# TinyArduino.net
KiCad netlist of a schematic drawn in Altium Designer
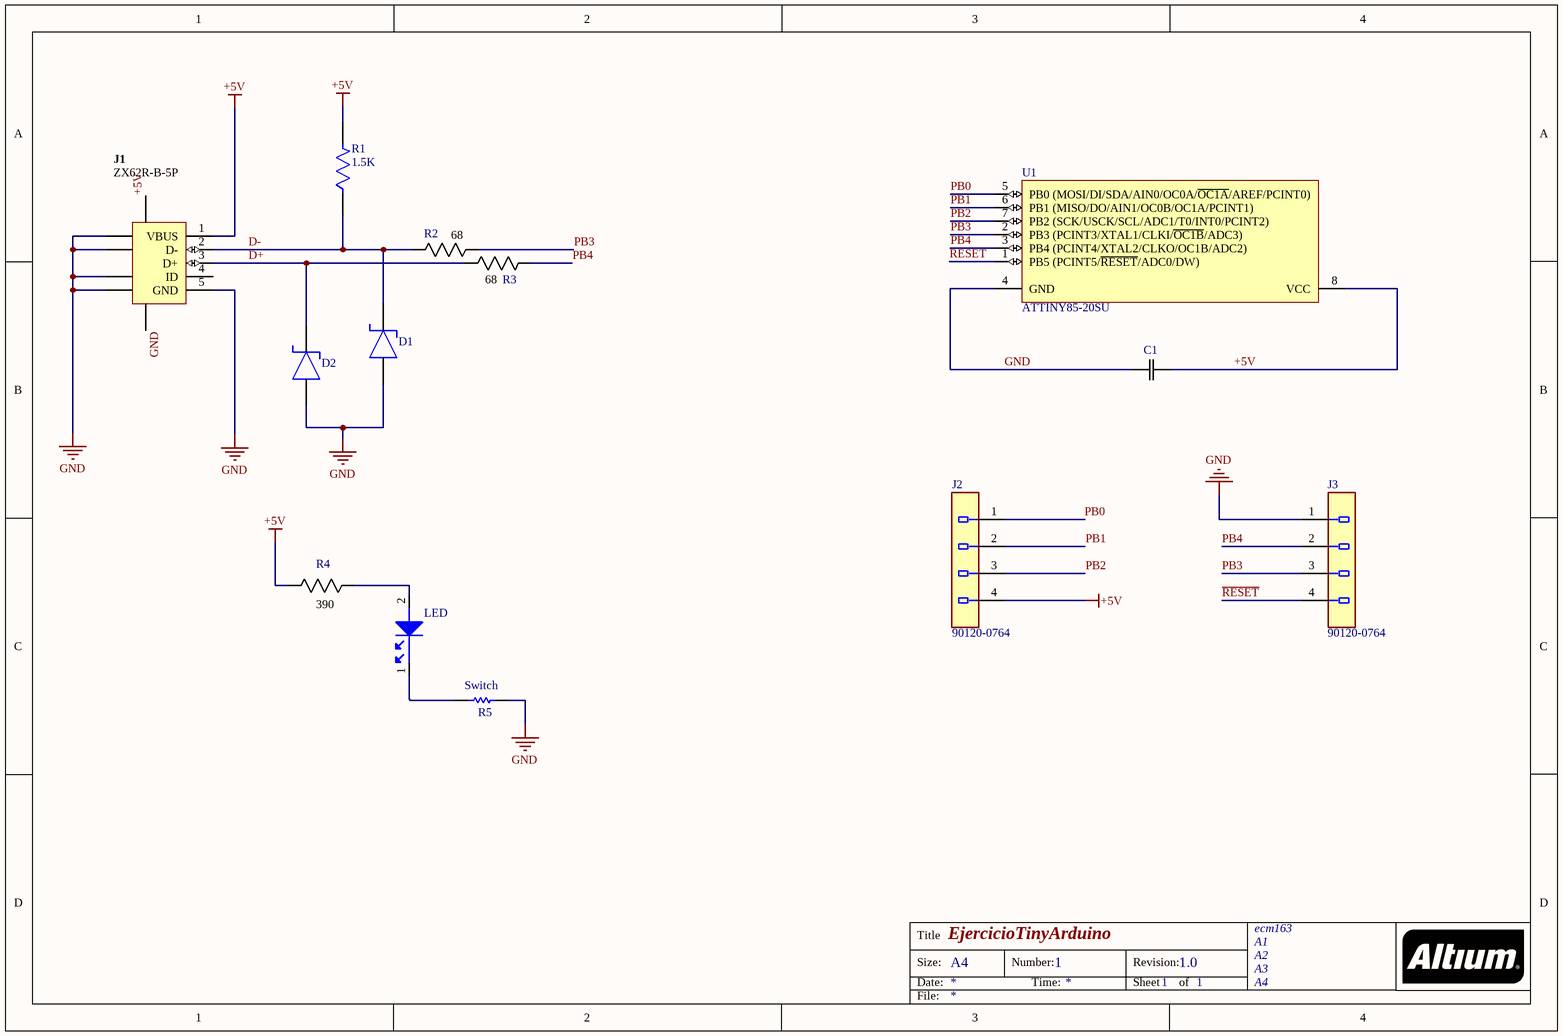
[diagram p0: TinyArduino.SchDoc]

(export (version "E")
  (design (tool "Eeschema 10.0.6"))
  (components
    (comp (ref "C1")
      (value "0603YC104JAT2A")
      (footprint "CAPC1608X90X35NL15T15")
      (description "Imported")
      (libsource (lib "0603YC104JAT2A") (part "0603YC104JAT2A"))
    )
    (comp (ref "D1")
      (value "Diodes Inc. B0540WS-7")
      (footprint "PCB-6tqbiewd2diqb4h5r69p-1")
      (description "DIODE SCHOTTKY 40V 500MA SOD323")
      (fields (field (name "MANUFACTURER") "Diodes") (field (name "MANUFACTURER PART NUMBER") "B0540WS-7"))
      (libsource (lib "B0540WS-7") (part "B0540WS-7"))
    )
    (comp (ref "D2")
      (value "Diodes Inc. B0540WS-7")
      (footprint "PCB-6tqbiewd2diqb4h5r69p-1")
      (description "DIODE SCHOTTKY 40V 500MA SOD323")
      (fields (field (name "MANUFACTURER") "Diodes") (field (name "MANUFACTURER PART NUMBER") "B0540WS-7"))
      (libsource (lib "B0540WS-7") (part "B0540WS-7"))
    )
    (comp (ref "J1")
      (value "ZX62R-B-5P")
      (footprint "HIRO-ZX62R-B-5P_V")
      (description "Connector; USBMicro-B,Reverse type, SMT; 5 Position; Right Angle")
      (libsource (lib "TinyArduino") (part "ZX62R-B-5P"))
    )
    (comp (ref "J2")
      (value "Conn_Molex_90120-0764_eec")
      (footprint "Molex_90120-0764_0")
      (description "CONN 4 Positions Header, Breakaway Connector 0.100\" (2.54mm) Through Hole Gold")
      (fields
        (field (name "MANUFACTURER") "Molex")
        (field (name "MOUSER PART NUMBER") "538-90120-0764")
        (field (name "PART NUMBER") "90120-0764")
      )
      (libsource (lib "") (part "Conn_Molex_90120-0764_eec_1"))
    )
    (comp (ref "J3")
      (value "Conn_Molex_90120-0764_eec")
      (footprint "Molex_90120-0764_0")
      (description "CONN 4 Positions Header, Breakaway Connector 0.100\" (2.54mm) Through Hole Gold")
      (fields
        (field (name "MANUFACTURER") "Molex")
        (field (name "MOUSER PART NUMBER") "538-90120-0764")
        (field (name "PART NUMBER") "90120-0764")
      )
      (libsource (lib "Molex90120-0764") (part "Conn_Molex_90120-0764_eec"))
    )
    (comp (ref "LED")
      (value "LED_AvagoHSMG-C190")
      (footprint "AVAG-HSMX-C190")
      (libsource (lib "LED_AVAG-HSMX-C190") (part "LED_AvagoHSMG-C190"))
    )
    (comp (ref "R1")
      (value "Res_Vishay_CRCW06031K50FKEA_eec")
      (footprint "RESC1609X50X30LL10T20")
      (description "RES 1.5k Ohm ±1% 0.1W, 1/10W Chip Resistor 0603 (1608 Metric) Automotive AEC-Q200 Thick Film")
      (fields
        (field (name "PART NUMBER") "CRCW06031K50FKEA")
        (field (name "VOLTAGE") "75V")
        (field (name "RESISTANCE") "1.5K")
      )
      (libsource (lib "RES_1.5K") (part "Res_Vishay_CRCW06031K50FKEA_eec"))
    )
    (comp (ref "R2")
      (value "68")
      (footprint "RESC1609X50X30ML10T20")
      (description "RES SMD 68 OHM 5% 1/10W 0603")
      (fields (field (name "MANUFACTURER_PART_NUMBER") "CRCW060368R0JNEA"))
      (libsource (lib "RES_68") (part "CRCW060368R0JNEA"))
    )
    (comp (ref "R3")
      (value "68")
      (footprint "RESC1609X50X30ML10T20")
      (description "RES SMD 68 OHM 5% 1/10W 0603")
      (fields (field (name "MANUFACTURER_PART_NUMBER") "CRCW060368R0JNEA"))
      (libsource (lib "RES_68") (part "CRCW060368R0JNEA"))
    )
    (comp (ref "R4")
      (value "390")
      (footprint "RESC1609X50X30LL10T20")
      (description "Imported")
      (fields
        (field (name "MANUFACTURER_PART_NUMBER") "CRCW0603390RFKEAHP")
        (field (name "Comment") "CRCW0603390RFKEA")
      )
      (libsource (lib "RES_390") (part "CRCW0603390RFKEA"))
    )
    (comp (ref "R5")
      (value "CRCW06030000Z0EA")
      (footprint "RESC1609X50X30LL10T20")
      (description "0Ω 1%")
      (libsource (lib "Switch_0603") (part "CRCW06030000Z0EA"))
    )
    (comp (ref "U1")
      (value "ATTINY85-20SU")
      (footprint "8S2_L")
      (libsource (lib "Microchip_Atmel_ATTINY85_20SU") (part "ATTINY85-20SU"))
    )
  )
  (nets
    (net (code "1") (name "+5V") (class "Default")
      (node (ref "C1") (pin "2") (pinfunction "2_2") (pintype "passive"))
      (node (ref "J1") (pin "1") (pinfunction "VBUS_1") (pintype "power_in"))
      (node (ref "J1") (pin "11") (pinfunction "SHLD_11") (pintype "passive"))
      (node (ref "J2") (pin "4") (pinfunction "4_4") (pintype "passive"))
      (node (ref "R1") (pin "2") (pinfunction "2_2") (pintype "passive"))
      (node (ref "R4") (pin "1") (pinfunction "1_1") (pintype "passive"))
      (node (ref "U1") (pin "8") (pinfunction "VCC_8") (pintype "power_in"))
    )
    (net (code "2") (name "/D+") (class "Default")
      (node (ref "D2") (pin "1") (pinfunction "1_1") (pintype "passive"))
      (node (ref "J1") (pin "3") (pinfunction "D+_3") (pintype "bidirectional"))
      (node (ref "R3") (pin "2") (pinfunction "2_2") (pintype "passive"))
    )
    (net (code "3") (name "/D-") (class "Default")
      (node (ref "D1") (pin "1") (pinfunction "1_1") (pintype "passive"))
      (node (ref "J1") (pin "2") (pinfunction "D-_2") (pintype "bidirectional"))
      (node (ref "R1") (pin "1") (pinfunction "1_1") (pintype "passive"))
      (node (ref "R2") (pin "2") (pinfunction "2_2") (pintype "passive"))
    )
    (net (code "4") (name "/PB0") (class "Default")
      (node (ref "J2") (pin "1") (pinfunction "1_1") (pintype "passive"))
      (node (ref "U1") (pin "5") (pinfunction "PB0_(MOSI/DI/SDA/AIN0/OC0A/~{OC1A}/AREF/PCINT0)_5") (pintype "bidirectional"))
    )
    (net (code "5") (name "/PB1") (class "Default")
      (node (ref "J2") (pin "2") (pinfunction "2_2") (pintype "passive"))
      (node (ref "U1") (pin "6") (pinfunction "PB1_(MISO/DO/AIN1/OC0B/OC1A/PCINT1)_6") (pintype "bidirectional"))
    )
    (net (code "6") (name "/PB2") (class "Default")
      (node (ref "J2") (pin "3") (pinfunction "3_3") (pintype "passive"))
      (node (ref "U1") (pin "7") (pinfunction "PB2_(SCK/USCK/SCL/ADC1/T0/INT0/PCINT2)_7") (pintype "bidirectional"))
    )
    (net (code "7") (name "/PB3") (class "Default")
      (node (ref "J3") (pin "3") (pinfunction "3_3") (pintype "passive"))
      (node (ref "R2") (pin "1") (pinfunction "1_1") (pintype "passive"))
      (node (ref "U1") (pin "2") (pinfunction "PB3_(PCINT3/XTAL1/CLKI/~{OC1B}/ADC3)_2") (pintype "bidirectional"))
    )
    (net (code "8") (name "/PB4") (class "Default")
      (node (ref "J3") (pin "2") (pinfunction "2_2") (pintype "passive"))
      (node (ref "R3") (pin "1") (pinfunction "1_1") (pintype "passive"))
      (node (ref "U1") (pin "3") (pinfunction "PB4_(PCINT4/XTAL2/CLKO/OC1B/ADC2)_3") (pintype "bidirectional"))
    )
    (net (code "9") (name "/~{RESET}") (class "Default")
      (node (ref "J3") (pin "4") (pinfunction "4_4") (pintype "passive"))
      (node (ref "U1") (pin "1") (pinfunction "PB5_(PCINT5/~{RESET}/ADC0/DW)_1") (pintype "bidirectional"))
    )
    (net (code "10") (name "GND") (class "Default")
      (node (ref "C1") (pin "1") (pinfunction "1_1") (pintype "passive"))
      (node (ref "D1") (pin "2") (pinfunction "2_2") (pintype "passive"))
      (node (ref "D2") (pin "2") (pinfunction "2_2") (pintype "passive"))
      (node (ref "J1") (pin "10") (pinfunction "SHLD_10") (pintype "passive"))
      (node (ref "J1") (pin "5") (pinfunction "GND_5") (pintype "power_in"))
      (node (ref "J1") (pin "6") (pinfunction "SHLD_6") (pintype "passive"))
      (node (ref "J1") (pin "7") (pinfunction "SHLD_7") (pintype "passive"))
      (node (ref "J1") (pin "8") (pinfunction "SHLD_8") (pintype "passive"))
      (node (ref "J1") (pin "9") (pinfunction "SHLD_9") (pintype "passive"))
      (node (ref "J3") (pin "1") (pinfunction "1_1") (pintype "passive"))
      (node (ref "R5") (pin "2") (pinfunction "2_2") (pintype "passive"))
      (node (ref "U1") (pin "4") (pinfunction "GND_4") (pintype "power_in"))
    )
    (net (code "11") (name "Net-(LED-Pad1)") (class "Default")
      (node (ref "LED") (pin "1") (pinfunction "1_1") (pintype "passive"))
      (node (ref "R5") (pin "1") (pinfunction "1_1") (pintype "passive"))
    )
    (net (code "12") (name "Net-(LED-Pad2)") (class "Default")
      (node (ref "LED") (pin "2") (pinfunction "2_2") (pintype "passive"))
      (node (ref "R4") (pin "2") (pinfunction "2_2") (pintype "passive"))
    )
    (net (code "13") (name "unconnected-(J1-ID-Pad4)") (class "Default")
      (node (ref "J1") (pin "4") (pinfunction "ID_4") (pintype "passive"))
    )
  )
)
